# Sensor_ESP32_1_0.net
KiCad netlist of a schematic drawn in EAGLE
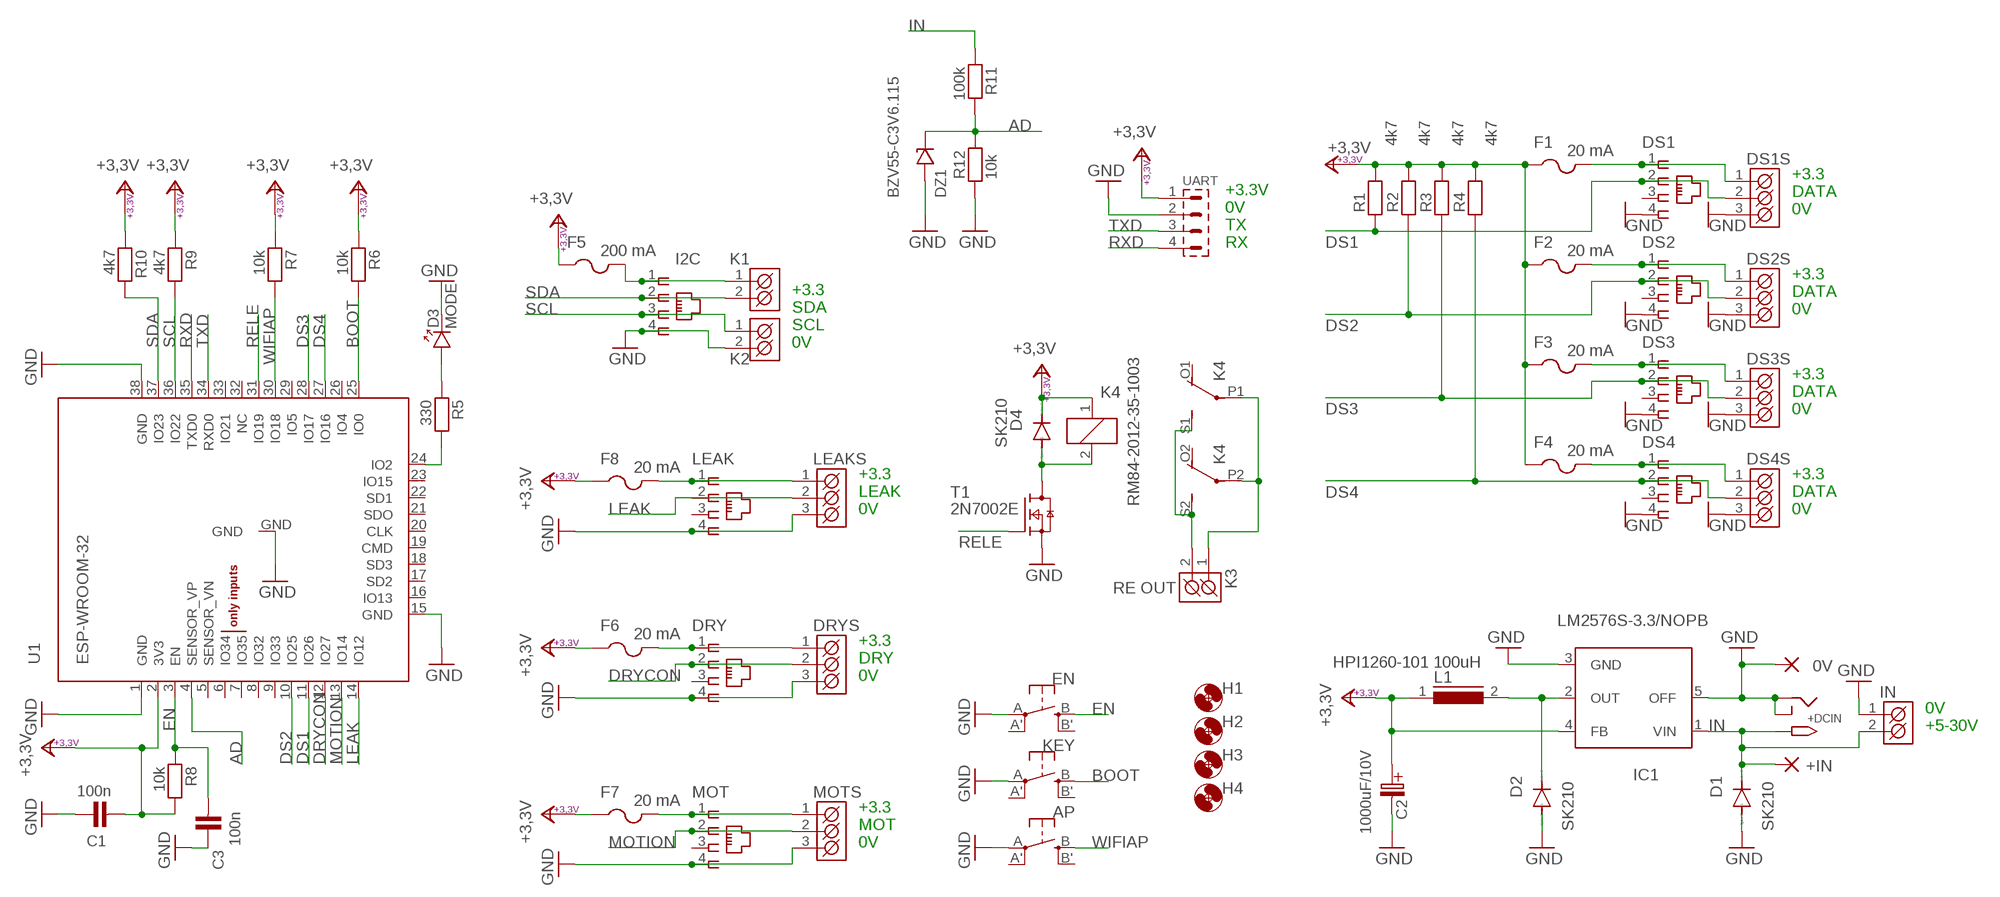
[diagram p0: schematic, sheet 1]

(export (version "E")
  (design (tool "Eeschema 10.0.6"))
  (components
    (comp (ref "+DCIN")
      (value "2.1MMJACKTHM")
      (footprint "eagle-import:PJ-102A")
      (libsource (lib "eagle-import") (part "2.1MMJACKTHM"))
    )
    (comp (ref "+IN")
      (value "SMD2")
      (footprint "eagle-import:SMD1,27-2,54")
      (libsource (lib "eagle-import") (part "SMD2"))
    )
    (comp (ref "0V")
      (value "SMD2")
      (footprint "eagle-import:SMD1,27-2,54")
      (libsource (lib "eagle-import") (part "SMD2"))
    )
    (comp (ref "AP")
      (value "SPST_TACT-EVQQ2")
      (footprint "eagle-import:EVQ-Q2")
      (libsource (lib "eagle-import") (part "SPST_TACT-EVQQ2"))
    )
    (comp (ref "C1")
      (value "100n")
      (footprint "eagle-import:1206")
      (libsource (lib "eagle-import") (part "C-KER_1206"))
    )
    (comp (ref "C2")
      (value "1000uF/10V")
      (footprint "eagle-import:C-EL_5")
      (libsource (lib "eagle-import") (part "C-EL_5"))
    )
    (comp (ref "C3")
      (value "100n")
      (footprint "eagle-import:1206")
      (libsource (lib "eagle-import") (part "C-KER_1206"))
    )
    (comp (ref "D1")
      (value "SK210")
      (footprint "eagle-import:SMB")
      (libsource (lib "eagle-import") (part "DIODE-SMB"))
    )
    (comp (ref "D2")
      (value "SK210")
      (footprint "eagle-import:SMB")
      (libsource (lib "eagle-import") (part "DIODE-SMB"))
    )
    (comp (ref "D3")
      (value "MODE")
      (footprint "eagle-import:P1206")
      (libsource (lib "eagle-import") (part "LED_1206"))
    )
    (comp (ref "D4")
      (value "SK210")
      (footprint "eagle-import:SMB")
      (libsource (lib "eagle-import") (part "DIODE-SMB"))
    )
    (comp (ref "DRY")
      (value "WEBP_6_1")
      (footprint "eagle-import:WEBP_6_1")
      (libsource (lib "eagle-import") (part "WEBP_6_1"))
    )
    (comp (ref "DRYS")
      (value "ARK550/3")
      (footprint "eagle-import:ARK550_3")
      (libsource (lib "eagle-import") (part "ARK550/3"))
    )
    (comp (ref "DS1")
      (value "WEBP_6_1")
      (footprint "eagle-import:WEBP_6_1")
      (libsource (lib "eagle-import") (part "WEBP_6_1"))
    )
    (comp (ref "DS1S")
      (value "ARK550/3")
      (footprint "eagle-import:ARK550_3")
      (libsource (lib "eagle-import") (part "ARK550/3"))
    )
    (comp (ref "DS2")
      (value "WEBP_6_1")
      (footprint "eagle-import:WEBP_6_1")
      (libsource (lib "eagle-import") (part "WEBP_6_1"))
    )
    (comp (ref "DS2S")
      (value "ARK550/3")
      (footprint "eagle-import:ARK550_3")
      (libsource (lib "eagle-import") (part "ARK550/3"))
    )
    (comp (ref "DS3")
      (value "WEBP_6_1")
      (footprint "eagle-import:WEBP_6_1")
      (libsource (lib "eagle-import") (part "WEBP_6_1"))
    )
    (comp (ref "DS3S")
      (value "ARK550/3")
      (footprint "eagle-import:ARK550_3")
      (libsource (lib "eagle-import") (part "ARK550/3"))
    )
    (comp (ref "DS4")
      (value "WEBP_6_1")
      (footprint "eagle-import:WEBP_6_1")
      (libsource (lib "eagle-import") (part "WEBP_6_1"))
    )
    (comp (ref "DS4S")
      (value "ARK550/3")
      (footprint "eagle-import:ARK550_3")
      (libsource (lib "eagle-import") (part "ARK550/3"))
    )
    (comp (ref "DZ1")
      (value "BZV55-C3V6.115")
      (footprint "eagle-import:SOD-80")
      (libsource (lib "eagle-import") (part "D-?-ZENERBZV55C_SMD_0,5W"))
    )
    (comp (ref "EN")
      (value "SPST_TACT-EVQQ2")
      (footprint "eagle-import:EVQ-Q2")
      (libsource (lib "eagle-import") (part "SPST_TACT-EVQQ2"))
    )
    (comp (ref "F1")
      (value "20 mA")
      (footprint "eagle-import:R1206")
      (libsource (lib "eagle-import") (part "PTCFUSE-1206"))
    )
    (comp (ref "F2")
      (value "20 mA")
      (footprint "eagle-import:R1206")
      (libsource (lib "eagle-import") (part "PTCFUSE-1206"))
    )
    (comp (ref "F3")
      (value "20 mA")
      (footprint "eagle-import:R1206")
      (libsource (lib "eagle-import") (part "PTCFUSE-1206"))
    )
    (comp (ref "F4")
      (value "20 mA")
      (footprint "eagle-import:R1206")
      (libsource (lib "eagle-import") (part "PTCFUSE-1206"))
    )
    (comp (ref "F5")
      (value "200 mA")
      (footprint "eagle-import:R1206")
      (libsource (lib "eagle-import") (part "PTCFUSE-1206"))
    )
    (comp (ref "F6")
      (value "20 mA")
      (footprint "eagle-import:R1206")
      (libsource (lib "eagle-import") (part "PTCFUSE-1206"))
    )
    (comp (ref "F7")
      (value "20 mA")
      (footprint "eagle-import:R1206")
      (libsource (lib "eagle-import") (part "PTCFUSE-1206"))
    )
    (comp (ref "F8")
      (value "20 mA")
      (footprint "eagle-import:R1206")
      (libsource (lib "eagle-import") (part "PTCFUSE-1206"))
    )
    (comp (ref "H1")
      (value "MOUNT-HOLE3.0")
      (footprint "eagle-import:3,0")
      (libsource (lib "eagle-import") (part "MOUNT-HOLE3.0"))
    )
    (comp (ref "H2")
      (value "MOUNT-HOLE3.0")
      (footprint "eagle-import:3,0")
      (libsource (lib "eagle-import") (part "MOUNT-HOLE3.0"))
    )
    (comp (ref "H3")
      (value "MOUNT-HOLE3.0")
      (footprint "eagle-import:3,0")
      (libsource (lib "eagle-import") (part "MOUNT-HOLE3.0"))
    )
    (comp (ref "H4")
      (value "MOUNT-HOLE3.0")
      (footprint "eagle-import:3,0")
      (libsource (lib "eagle-import") (part "MOUNT-HOLE3.0"))
    )
    (comp (ref "I2C")
      (value "WEBP_6_1")
      (footprint "eagle-import:WEBP_6_1")
      (libsource (lib "eagle-import") (part "WEBP_6_1"))
    )
    (comp (ref "IC1")
      (value "LM2576S-3.3/NOPB")
      (footprint "eagle-import:TO263-5")
      (libsource (lib "eagle-import") (part "LM2576S"))
    )
    (comp (ref "IN")
      (value "ARK550/2")
      (footprint "eagle-import:ARK550_2")
      (libsource (lib "eagle-import") (part "ARK550/2"))
    )
    (comp (ref "K1")
      (value "ARK550/2")
      (footprint "eagle-import:ARK550_2")
      (libsource (lib "eagle-import") (part "ARK550/2"))
    )
    (comp (ref "K2")
      (value "ARK550/2")
      (footprint "eagle-import:ARK550_2")
      (libsource (lib "eagle-import") (part "ARK550/2"))
    )
    (comp (ref "K3")
      (value "RE OUT")
      (footprint "eagle-import:ARK500_2")
      (libsource (lib "eagle-import") (part "ARK500/2"))
    )
    (comp (ref "K4")
      (value "RM84-2012-35-1003")
      (footprint "eagle-import:G2R2")
      (fields (field (name "MF") "OMRON COMPONENTS USA") (field (name "MPN") "G2R-2-DC6"))
      (libsource (lib "eagle-import") (part "G2R2"))
    )
    (comp (ref "KEY")
      (value "SPST_TACT-EVQQ2")
      (footprint "eagle-import:EVQ-Q2")
      (libsource (lib "eagle-import") (part "SPST_TACT-EVQQ2"))
    )
    (comp (ref "L1")
      (value "HPI1260-101 100uH")
      (footprint "eagle-import:DR125")
      (libsource (lib "eagle-import") (part "DR125"))
    )
    (comp (ref "LEAK")
      (value "WEBP_6_1")
      (footprint "eagle-import:WEBP_6_1")
      (libsource (lib "eagle-import") (part "WEBP_6_1"))
    )
    (comp (ref "LEAKS")
      (value "ARK550/3")
      (footprint "eagle-import:ARK550_3")
      (libsource (lib "eagle-import") (part "ARK550/3"))
    )
    (comp (ref "MOT")
      (value "WEBP_6_1")
      (footprint "eagle-import:WEBP_6_1")
      (libsource (lib "eagle-import") (part "WEBP_6_1"))
    )
    (comp (ref "MOTS")
      (value "ARK550/3")
      (footprint "eagle-import:ARK550_3")
      (libsource (lib "eagle-import") (part "ARK550/3"))
    )
    (comp (ref "R1")
      (value "4k7")
      (footprint "eagle-import:1206")
      (libsource (lib "eagle-import") (part "R_1206"))
    )
    (comp (ref "R2")
      (value "4k7")
      (footprint "eagle-import:1206")
      (libsource (lib "eagle-import") (part "R_1206"))
    )
    (comp (ref "R3")
      (value "4k7")
      (footprint "eagle-import:1206")
      (libsource (lib "eagle-import") (part "R_1206"))
    )
    (comp (ref "R4")
      (value "4k7")
      (footprint "eagle-import:1206")
      (libsource (lib "eagle-import") (part "R_1206"))
    )
    (comp (ref "R5")
      (value "330")
      (footprint "eagle-import:1206")
      (libsource (lib "eagle-import") (part "R_1206"))
    )
    (comp (ref "R6")
      (value "10k")
      (footprint "eagle-import:1206")
      (libsource (lib "eagle-import") (part "R_1206"))
    )
    (comp (ref "R7")
      (value "10k")
      (footprint "eagle-import:1206")
      (libsource (lib "eagle-import") (part "R_1206"))
    )
    (comp (ref "R8")
      (value "10k")
      (footprint "eagle-import:1206")
      (libsource (lib "eagle-import") (part "R_1206"))
    )
    (comp (ref "R9")
      (value "4k7")
      (footprint "eagle-import:1206")
      (libsource (lib "eagle-import") (part "R_1206"))
    )
    (comp (ref "R10")
      (value "4k7")
      (footprint "eagle-import:1206")
      (libsource (lib "eagle-import") (part "R_1206"))
    )
    (comp (ref "R11")
      (value "100k")
      (footprint "eagle-import:1206")
      (libsource (lib "eagle-import") (part "R_1206"))
    )
    (comp (ref "R12")
      (value "10k")
      (footprint "eagle-import:1206")
      (libsource (lib "eagle-import") (part "R_1206"))
    )
    (comp (ref "T1")
      (value "2N7002E")
      (footprint "eagle-import:SOT23")
      (libsource (lib "eagle-import") (part "2N7002E"))
    )
    (comp (ref "U1")
      (value "ESP-WROOM-32")
      (footprint "eagle-import:ESP-WROOM-32")
      (libsource (lib "eagle-import") (part "ESP-WROOM-32"))
    )
    (comp (ref "UART")
      (value "S1G4_JUMP")
      (footprint "eagle-import:S1G4_JUM")
      (libsource (lib "eagle-import") (part "S1G4_JUMP"))
    )
  )
  (nets
    (net (code "1") (name "+3,3V") (class "Default")
      (node (ref "C1") (pin "2") (pinfunction "2_2") (pintype "passive"))
      (node (ref "C2") (pin "C+") (pinfunction "C_EL+_C+") (pintype "passive"))
      (node (ref "D4") (pin "C") (pinfunction "C_C") (pintype "passive"))
      (node (ref "F1") (pin "1") (pinfunction "1_1") (pintype "passive"))
      (node (ref "F2") (pin "1") (pinfunction "1_1") (pintype "passive"))
      (node (ref "F3") (pin "1") (pinfunction "1_1") (pintype "passive"))
      (node (ref "F4") (pin "1") (pinfunction "1_1") (pintype "passive"))
      (node (ref "F5") (pin "1") (pinfunction "1_1") (pintype "passive"))
      (node (ref "F6") (pin "1") (pinfunction "1_1") (pintype "passive"))
      (node (ref "F7") (pin "1") (pinfunction "1_1") (pintype "passive"))
      (node (ref "F8") (pin "1") (pinfunction "1_1") (pintype "passive"))
      (node (ref "IC1") (pin "4") (pinfunction "FB_4") (pintype "input"))
      (node (ref "K4") (pin "1") (pinfunction "1_1") (pintype "passive"))
      (node (ref "L1") (pin "1") (pinfunction "1_1") (pintype "passive"))
      (node (ref "R1") (pin "2") (pinfunction "2_2") (pintype "passive"))
      (node (ref "R10") (pin "1") (pinfunction "1_1") (pintype "passive"))
      (node (ref "R2") (pin "2") (pinfunction "2_2") (pintype "passive"))
      (node (ref "R3") (pin "2") (pinfunction "2_2") (pintype "passive"))
      (node (ref "R4") (pin "2") (pinfunction "2_2") (pintype "passive"))
      (node (ref "R6") (pin "1") (pinfunction "1_1") (pintype "passive"))
      (node (ref "R7") (pin "1") (pinfunction "1_1") (pintype "passive"))
      (node (ref "R8") (pin "2") (pinfunction "2_2") (pintype "passive"))
      (node (ref "R9") (pin "1") (pinfunction "1_1") (pintype "passive"))
      (node (ref "U1") (pin "2") (pinfunction "3V3_2") (pintype "bidirectional"))
      (node (ref "UART") (pin "1") (pinfunction "1_1") (pintype "passive"))
    )
    (net (code "2") (name "/AD") (class "Default")
      (node (ref "DZ1") (pin "K") (pinfunction "K_K") (pintype "passive"))
      (node (ref "R11") (pin "2") (pinfunction "2_2") (pintype "passive"))
      (node (ref "R12") (pin "2") (pinfunction "2_2") (pintype "passive"))
      (node (ref "U1") (pin "4") (pinfunction "SENSOR_VP_4") (pintype "input"))
    )
    (net (code "3") (name "/BOOT") (class "Default")
      (node (ref "KEY") (pin "B") (pinfunction "S_B") (pintype "passive"))
      (node (ref "R6") (pin "2") (pinfunction "2_2") (pintype "passive"))
      (node (ref "U1") (pin "25") (pinfunction "IO0_25") (pintype "bidirectional"))
    )
    (net (code "4") (name "/DRYCON") (class "Default")
      (node (ref "DRY") (pin "2") (pinfunction "2_2") (pintype "passive"))
      (node (ref "DRYS") (pin "2") (pinfunction "K2_2") (pintype "passive"))
      (node (ref "U1") (pin "12") (pinfunction "IO27_12") (pintype "bidirectional"))
    )
    (net (code "5") (name "/DS1") (class "Default")
      (node (ref "DS1") (pin "2") (pinfunction "2_2") (pintype "passive"))
      (node (ref "DS1S") (pin "2") (pinfunction "K2_2") (pintype "passive"))
      (node (ref "R1") (pin "1") (pinfunction "1_1") (pintype "passive"))
      (node (ref "U1") (pin "11") (pinfunction "IO26_11") (pintype "bidirectional"))
    )
    (net (code "6") (name "/DS2") (class "Default")
      (node (ref "DS2") (pin "2") (pinfunction "2_2") (pintype "passive"))
      (node (ref "DS2S") (pin "2") (pinfunction "K2_2") (pintype "passive"))
      (node (ref "R2") (pin "1") (pinfunction "1_1") (pintype "passive"))
      (node (ref "U1") (pin "10") (pinfunction "IO25_10") (pintype "bidirectional"))
    )
    (net (code "7") (name "/DS3") (class "Default")
      (node (ref "DS3") (pin "2") (pinfunction "2_2") (pintype "passive"))
      (node (ref "DS3S") (pin "2") (pinfunction "K2_2") (pintype "passive"))
      (node (ref "R3") (pin "1") (pinfunction "1_1") (pintype "passive"))
      (node (ref "U1") (pin "28") (pinfunction "IO17_28") (pintype "bidirectional"))
    )
    (net (code "8") (name "/DS4") (class "Default")
      (node (ref "DS4") (pin "2") (pinfunction "2_2") (pintype "passive"))
      (node (ref "DS4S") (pin "2") (pinfunction "K2_2") (pintype "passive"))
      (node (ref "R4") (pin "1") (pinfunction "1_1") (pintype "passive"))
      (node (ref "U1") (pin "27") (pinfunction "IO16_27") (pintype "bidirectional"))
    )
    (net (code "9") (name "/EN") (class "Default")
      (node (ref "C3") (pin "2") (pinfunction "2_2") (pintype "passive"))
      (node (ref "EN") (pin "B") (pinfunction "S_B") (pintype "passive"))
      (node (ref "R8") (pin "1") (pinfunction "1_1") (pintype "passive"))
      (node (ref "U1") (pin "3") (pinfunction "EN_3") (pintype "bidirectional"))
    )
    (net (code "10") (name "/IN") (class "Default")
      (node (ref "+DCIN") (pin "TIP") (pinfunction "TIP_TIP") (pintype "bidirectional"))
      (node (ref "+IN") (pin "1") (pinfunction "P_1") (pintype "passive"))
      (node (ref "D1") (pin "C") (pinfunction "C_C") (pintype "passive"))
      (node (ref "IC1") (pin "1") (pinfunction "VIN_1") (pintype "power_in"))
      (node (ref "IN") (pin "2") (pinfunction "K2_2") (pintype "passive"))
      (node (ref "R11") (pin "1") (pinfunction "1_1") (pintype "passive"))
    )
    (net (code "11") (name "/LEAK") (class "Default")
      (node (ref "LEAK") (pin "2") (pinfunction "2_2") (pintype "passive"))
      (node (ref "LEAKS") (pin "2") (pinfunction "K2_2") (pintype "passive"))
      (node (ref "U1") (pin "14") (pinfunction "IO12_14") (pintype "bidirectional"))
    )
    (net (code "12") (name "/MOTION") (class "Default")
      (node (ref "MOT") (pin "2") (pinfunction "2_2") (pintype "passive"))
      (node (ref "MOTS") (pin "2") (pinfunction "K2_2") (pintype "passive"))
      (node (ref "U1") (pin "13") (pinfunction "IO14_13") (pintype "bidirectional"))
    )
    (net (code "13") (name "/RELE") (class "Default")
      (node (ref "T1") (pin "1") (pinfunction "G_1") (pintype "passive"))
      (node (ref "U1") (pin "31") (pinfunction "IO19_31") (pintype "bidirectional"))
    )
    (net (code "14") (name "/RXD") (class "Default")
      (node (ref "U1") (pin "35") (pinfunction "TXD0_35") (pintype "bidirectional"))
      (node (ref "UART") (pin "4") (pinfunction "4_4") (pintype "passive"))
    )
    (net (code "15") (name "/SCL") (class "Default")
      (node (ref "I2C") (pin "3") (pinfunction "3_3") (pintype "passive"))
      (node (ref "K2") (pin "1") (pinfunction "K1_1") (pintype "passive"))
      (node (ref "R9") (pin "2") (pinfunction "2_2") (pintype "passive"))
      (node (ref "U1") (pin "36") (pinfunction "IO22_36") (pintype "bidirectional"))
    )
    (net (code "16") (name "/SDA") (class "Default")
      (node (ref "I2C") (pin "2") (pinfunction "2_2") (pintype "passive"))
      (node (ref "K1") (pin "2") (pinfunction "K2_2") (pintype "passive"))
      (node (ref "R10") (pin "2") (pinfunction "2_2") (pintype "passive"))
      (node (ref "U1") (pin "37") (pinfunction "IO23_37") (pintype "bidirectional"))
    )
    (net (code "17") (name "/TXD") (class "Default")
      (node (ref "U1") (pin "34") (pinfunction "RXD0_34") (pintype "bidirectional"))
      (node (ref "UART") (pin "3") (pinfunction "3_3") (pintype "passive"))
    )
    (net (code "18") (name "/WIFIAP") (class "Default")
      (node (ref "AP") (pin "B") (pinfunction "S_B") (pintype "passive"))
      (node (ref "R7") (pin "2") (pinfunction "2_2") (pintype "passive"))
      (node (ref "U1") (pin "30") (pinfunction "IO18_30") (pintype "bidirectional"))
    )
    (net (code "19") (name "GND") (class "Default")
      (node (ref "+DCIN") (pin "RING") (pinfunction "RING_RING") (pintype "bidirectional"))
      (node (ref "+DCIN") (pin "RING_SW") (pinfunction "RING_SW_RING_SW") (pintype "bidirectional"))
      (node (ref "0V") (pin "1") (pinfunction "P_1") (pintype "passive"))
      (node (ref "AP") (pin "A") (pinfunction "P_A") (pintype "passive"))
      (node (ref "C1") (pin "1") (pinfunction "1_1") (pintype "passive"))
      (node (ref "C2") (pin "C-") (pinfunction "C_EL-_C-") (pintype "passive"))
      (node (ref "C3") (pin "1") (pinfunction "1_1") (pintype "passive"))
      (node (ref "D1") (pin "A") (pinfunction "A_A") (pintype "passive"))
      (node (ref "D2") (pin "A") (pinfunction "A_A") (pintype "passive"))
      (node (ref "D3") (pin "K") (pinfunction "K_K") (pintype "passive"))
      (node (ref "DRY") (pin "4") (pinfunction "4_4") (pintype "passive"))
      (node (ref "DRYS") (pin "3") (pinfunction "K3_3") (pintype "passive"))
      (node (ref "DS1") (pin "4") (pinfunction "4_4") (pintype "passive"))
      (node (ref "DS1S") (pin "3") (pinfunction "K3_3") (pintype "passive"))
      (node (ref "DS2") (pin "4") (pinfunction "4_4") (pintype "passive"))
      (node (ref "DS2S") (pin "3") (pinfunction "K3_3") (pintype "passive"))
      (node (ref "DS3") (pin "4") (pinfunction "4_4") (pintype "passive"))
      (node (ref "DS3S") (pin "3") (pinfunction "K3_3") (pintype "passive"))
      (node (ref "DS4") (pin "4") (pinfunction "4_4") (pintype "passive"))
      (node (ref "DS4S") (pin "3") (pinfunction "K3_3") (pintype "passive"))
      (node (ref "DZ1") (pin "A") (pinfunction "A_A") (pintype "passive"))
      (node (ref "EN") (pin "A") (pinfunction "P_A") (pintype "passive"))
      (node (ref "I2C") (pin "4") (pinfunction "4_4") (pintype "passive"))
      (node (ref "IC1") (pin "3") (pinfunction "GND_3") (pintype "power_in"))
      (node (ref "IC1") (pin "5") (pinfunction "OFF_5") (pintype "input"))
      (node (ref "IN") (pin "1") (pinfunction "K1_1") (pintype "passive"))
      (node (ref "K2") (pin "2") (pinfunction "K2_2") (pintype "passive"))
      (node (ref "KEY") (pin "A") (pinfunction "P_A") (pintype "passive"))
      (node (ref "LEAK") (pin "4") (pinfunction "4_4") (pintype "passive"))
      (node (ref "LEAKS") (pin "3") (pinfunction "K3_3") (pintype "passive"))
      (node (ref "MOT") (pin "4") (pinfunction "4_4") (pintype "passive"))
      (node (ref "MOTS") (pin "3") (pinfunction "K3_3") (pintype "passive"))
      (node (ref "R12") (pin "1") (pinfunction "1_1") (pintype "passive"))
      (node (ref "T1") (pin "2") (pinfunction "S_2") (pintype "passive"))
      (node (ref "U1") (pin "1") (pinfunction "GND_1") (pintype "bidirectional"))
      (node (ref "U1") (pin "15") (pinfunction "GND_15") (pintype "bidirectional"))
      (node (ref "U1") (pin "38") (pinfunction "GND_38") (pintype "bidirectional"))
      (node (ref "U1") (pin "GND") (pinfunction "GND_GND") (pintype "bidirectional"))
      (node (ref "UART") (pin "2") (pinfunction "2_2") (pintype "passive"))
    )
    (net (code "20") (name "Net-(D3-PadA)") (class "Default")
      (node (ref "D3") (pin "A") (pinfunction "A_A") (pintype "passive"))
      (node (ref "R5") (pin "1") (pinfunction "1_1") (pintype "passive"))
    )
    (net (code "21") (name "Net-(DRYS-K1)") (class "Default")
      (node (ref "DRY") (pin "1") (pinfunction "1_1") (pintype "passive"))
      (node (ref "DRYS") (pin "1") (pinfunction "K1_1") (pintype "passive"))
      (node (ref "F6") (pin "2") (pinfunction "2_2") (pintype "passive"))
    )
    (net (code "22") (name "Net-(DS1S-K1)") (class "Default")
      (node (ref "DS1") (pin "1") (pinfunction "1_1") (pintype "passive"))
      (node (ref "DS1S") (pin "1") (pinfunction "K1_1") (pintype "passive"))
      (node (ref "F1") (pin "2") (pinfunction "2_2") (pintype "passive"))
    )
    (net (code "23") (name "Net-(DS2S-K1)") (class "Default")
      (node (ref "DS2") (pin "1") (pinfunction "1_1") (pintype "passive"))
      (node (ref "DS2S") (pin "1") (pinfunction "K1_1") (pintype "passive"))
      (node (ref "F2") (pin "2") (pinfunction "2_2") (pintype "passive"))
    )
    (net (code "24") (name "Net-(DS3S-K1)") (class "Default")
      (node (ref "DS3") (pin "1") (pinfunction "1_1") (pintype "passive"))
      (node (ref "DS3S") (pin "1") (pinfunction "K1_1") (pintype "passive"))
      (node (ref "F3") (pin "2") (pinfunction "2_2") (pintype "passive"))
    )
    (net (code "25") (name "Net-(DS4S-K1)") (class "Default")
      (node (ref "DS4") (pin "1") (pinfunction "1_1") (pintype "passive"))
      (node (ref "DS4S") (pin "1") (pinfunction "K1_1") (pintype "passive"))
      (node (ref "F4") (pin "2") (pinfunction "2_2") (pintype "passive"))
    )
    (net (code "26") (name "Net-(IC1-OUT)") (class "Default")
      (node (ref "D2") (pin "C") (pinfunction "C_C") (pintype "passive"))
      (node (ref "IC1") (pin "2") (pinfunction "OUT_2") (pintype "output"))
      (node (ref "L1") (pin "2") (pinfunction "2_2") (pintype "passive"))
    )
    (net (code "27") (name "Net-(K1-K1)") (class "Default")
      (node (ref "F5") (pin "2") (pinfunction "2_2") (pintype "passive"))
      (node (ref "I2C") (pin "1") (pinfunction "1_1") (pintype "passive"))
      (node (ref "K1") (pin "1") (pinfunction "K1_1") (pintype "passive"))
    )
    (net (code "28") (name "Net-(K3-K1)") (class "Default")
      (node (ref "K3") (pin "1") (pinfunction "K1_1") (pintype "passive"))
      (node (ref "K4") (pin "P1") (pinfunction "P_P1") (pintype "passive"))
      (node (ref "K4") (pin "P2") (pinfunction "P_P2") (pintype "passive"))
    )
    (net (code "29") (name "Net-(K3-K2)") (class "Default")
      (node (ref "K3") (pin "2") (pinfunction "K2_2") (pintype "passive"))
      (node (ref "K4") (pin "S1") (pinfunction "S_S1") (pintype "passive"))
      (node (ref "K4") (pin "S2") (pinfunction "S_S2") (pintype "passive"))
    )
    (net (code "30") (name "Net-(LEAKS-K1)") (class "Default")
      (node (ref "F8") (pin "2") (pinfunction "2_2") (pintype "passive"))
      (node (ref "LEAK") (pin "1") (pinfunction "1_1") (pintype "passive"))
      (node (ref "LEAKS") (pin "1") (pinfunction "K1_1") (pintype "passive"))
    )
    (net (code "31") (name "Net-(MOTS-K1)") (class "Default")
      (node (ref "F7") (pin "2") (pinfunction "2_2") (pintype "passive"))
      (node (ref "MOT") (pin "1") (pinfunction "1_1") (pintype "passive"))
      (node (ref "MOTS") (pin "1") (pinfunction "K1_1") (pintype "passive"))
    )
    (net (code "32") (name "Net-(T1-D)") (class "Default")
      (node (ref "D4") (pin "A") (pinfunction "A_A") (pintype "passive"))
      (node (ref "K4") (pin "2") (pinfunction "2_2") (pintype "passive"))
      (node (ref "T1") (pin "3") (pinfunction "D_3") (pintype "passive"))
    )
    (net (code "33") (name "Net-(U1-IO2)") (class "Default")
      (node (ref "R5") (pin "2") (pinfunction "2_2") (pintype "passive"))
      (node (ref "U1") (pin "24") (pinfunction "IO2_24") (pintype "bidirectional"))
    )
    (net (code "34") (name "unconnected-(AP-P1-PadA')") (class "Default")
      (node (ref "AP") (pin "A'") (pinfunction "P1_A'") (pintype "passive"))
    )
    (net (code "35") (name "unconnected-(AP-S1-PadB')") (class "Default")
      (node (ref "AP") (pin "B'") (pinfunction "S1_B'") (pintype "passive"))
    )
    (net (code "36") (name "unconnected-(DRY-Pad3)") (class "Default")
      (node (ref "DRY") (pin "3") (pinfunction "3_3") (pintype "passive"))
    )
    (net (code "37") (name "unconnected-(DS1-Pad3)") (class "Default")
      (node (ref "DS1") (pin "3") (pinfunction "3_3") (pintype "passive"))
    )
    (net (code "38") (name "unconnected-(DS2-Pad3)") (class "Default")
      (node (ref "DS2") (pin "3") (pinfunction "3_3") (pintype "passive"))
    )
    (net (code "39") (name "unconnected-(DS3-Pad3)") (class "Default")
      (node (ref "DS3") (pin "3") (pinfunction "3_3") (pintype "passive"))
    )
    (net (code "40") (name "unconnected-(DS4-Pad3)") (class "Default")
      (node (ref "DS4") (pin "3") (pinfunction "3_3") (pintype "passive"))
    )
    (net (code "41") (name "unconnected-(EN-P1-PadA')") (class "Default")
      (node (ref "EN") (pin "A'") (pinfunction "P1_A'") (pintype "passive"))
    )
    (net (code "42") (name "unconnected-(EN-S1-PadB')") (class "Default")
      (node (ref "EN") (pin "B'") (pinfunction "S1_B'") (pintype "passive"))
    )
    (net (code "43") (name "unconnected-(K4B-O-PadO1)") (class "Default")
      (node (ref "K4") (pin "O1") (pinfunction "O_O1") (pintype "passive"))
    )
    (net (code "44") (name "unconnected-(K4C-O-PadO2)") (class "Default")
      (node (ref "K4") (pin "O2") (pinfunction "O_O2") (pintype "passive"))
    )
    (net (code "45") (name "unconnected-(KEY-P1-PadA')") (class "Default")
      (node (ref "KEY") (pin "A'") (pinfunction "P1_A'") (pintype "passive"))
    )
    (net (code "46") (name "unconnected-(KEY-S1-PadB')") (class "Default")
      (node (ref "KEY") (pin "B'") (pinfunction "S1_B'") (pintype "passive"))
    )
    (net (code "47") (name "unconnected-(LEAK-Pad3)") (class "Default")
      (node (ref "LEAK") (pin "3") (pinfunction "3_3") (pintype "passive"))
    )
    (net (code "48") (name "unconnected-(MOT-Pad3)") (class "Default")
      (node (ref "MOT") (pin "3") (pinfunction "3_3") (pintype "passive"))
    )
    (net (code "49") (name "unconnected-(U1-CLK-Pad20)") (class "Default")
      (node (ref "U1") (pin "20") (pinfunction "CLK_20") (pintype "bidirectional"))
    )
    (net (code "50") (name "unconnected-(U1-CMD-Pad19)") (class "Default")
      (node (ref "U1") (pin "19") (pinfunction "CMD_19") (pintype "bidirectional"))
    )
    (net (code "51") (name "unconnected-(U1-IO4-Pad26)") (class "Default")
      (node (ref "U1") (pin "26") (pinfunction "IO4_26") (pintype "bidirectional"))
    )
    (net (code "52") (name "unconnected-(U1-IO5-Pad29)") (class "Default")
      (node (ref "U1") (pin "29") (pinfunction "IO5_29") (pintype "bidirectional"))
    )
    (net (code "53") (name "unconnected-(U1-IO13-Pad16)") (class "Default")
      (node (ref "U1") (pin "16") (pinfunction "IO13_16") (pintype "bidirectional"))
    )
    (net (code "54") (name "unconnected-(U1-IO15-Pad23)") (class "Default")
      (node (ref "U1") (pin "23") (pinfunction "IO15_23") (pintype "bidirectional"))
    )
    (net (code "55") (name "unconnected-(U1-IO21-Pad33)") (class "Default")
      (node (ref "U1") (pin "33") (pinfunction "IO21_33") (pintype "bidirectional"))
    )
    (net (code "56") (name "unconnected-(U1-IO32-Pad8)") (class "Default")
      (node (ref "U1") (pin "8") (pinfunction "IO32_8") (pintype "bidirectional"))
    )
    (net (code "57") (name "unconnected-(U1-IO33-Pad9)") (class "Default")
      (node (ref "U1") (pin "9") (pinfunction "IO33_9") (pintype "bidirectional"))
    )
    (net (code "58") (name "unconnected-(U1-IO34-Pad6)") (class "Default")
      (node (ref "U1") (pin "6") (pinfunction "IO34_6") (pintype "input"))
    )
    (net (code "59") (name "unconnected-(U1-IO35-Pad7)") (class "Default")
      (node (ref "U1") (pin "7") (pinfunction "IO35_7") (pintype "input"))
    )
    (net (code "60") (name "unconnected-(U1-NC-Pad32)") (class "Default")
      (node (ref "U1") (pin "32") (pinfunction "NC_32") (pintype "bidirectional"))
    )
    (net (code "61") (name "unconnected-(U1-SD1-Pad22)") (class "Default")
      (node (ref "U1") (pin "22") (pinfunction "SD1_22") (pintype "bidirectional"))
    )
    (net (code "62") (name "unconnected-(U1-SD2-Pad17)") (class "Default")
      (node (ref "U1") (pin "17") (pinfunction "SD2_17") (pintype "bidirectional"))
    )
    (net (code "63") (name "unconnected-(U1-SD3-Pad18)") (class "Default")
      (node (ref "U1") (pin "18") (pinfunction "SD3_18") (pintype "bidirectional"))
    )
    (net (code "64") (name "unconnected-(U1-SDO-Pad21)") (class "Default")
      (node (ref "U1") (pin "21") (pinfunction "SDO_21") (pintype "bidirectional"))
    )
    (net (code "65") (name "unconnected-(U1-SENSOR_VN-Pad5)") (class "Default")
      (node (ref "U1") (pin "5") (pinfunction "SENSOR_VN_5") (pintype "input"))
    )
  )
)
